# design.net
KiCad netlist of a schematic drawn in Altium Designer
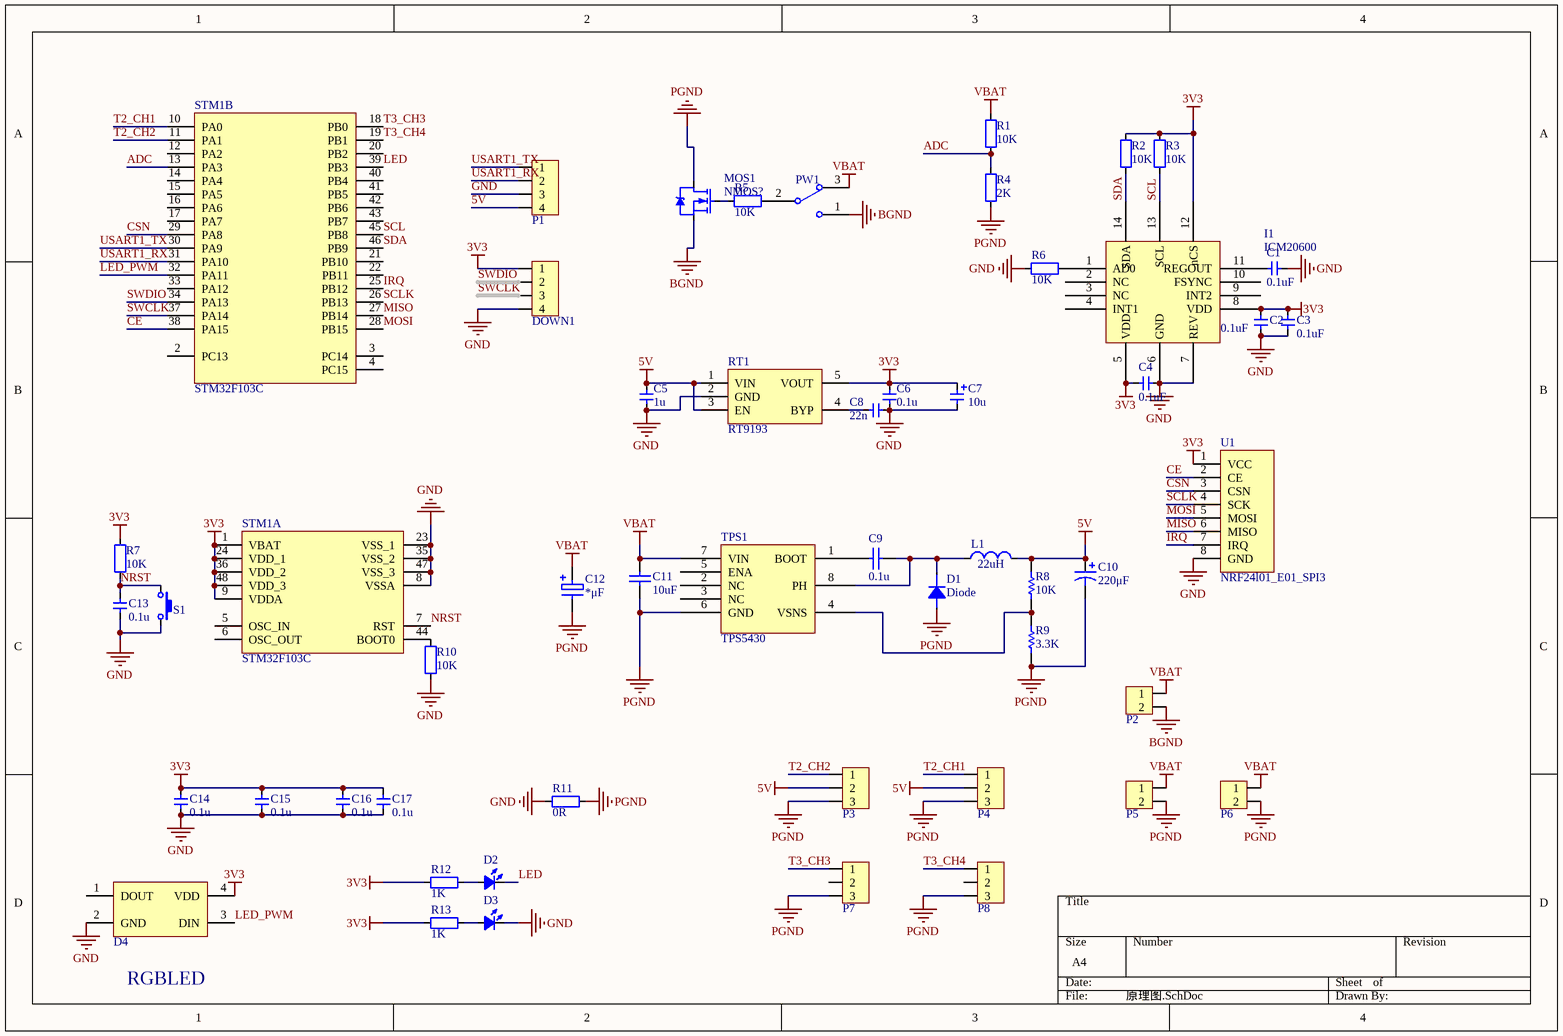
[diagram p0: 原理图.SchDoc]

(export (version "E")
  (design (tool "Eeschema 10.0.6"))
  (components
    (comp (ref "C1")
      (value "0.1uF")
      (footprint "PCB_PassiveCap:CAP_0603")
      (description "Capacitor")
      (fields (field (name "Comment") "Cap_0603"))
      (libsource (lib "SCH_Passive") (part "Cap_0603"))
    )
    (comp (ref "C2")
      (value "0.1uF")
      (footprint "PCB_PassiveCap:CAP_0603")
      (description "Capacitor")
      (fields (field (name "Comment") "Cap_0603"))
      (libsource (lib "SCH_Passive") (part "Cap_0603"))
    )
    (comp (ref "C3")
      (value "0.1uF")
      (footprint "PCB_PassiveCap:CAP_0603")
      (description "Capacitor")
      (fields (field (name "Comment") "Cap_0603"))
      (libsource (lib "SCH_Passive") (part "Cap_0603"))
    )
    (comp (ref "C4")
      (value "0.1uF")
      (footprint "PCB_PassiveCap:CAP_0603")
      (description "Capacitor")
      (fields (field (name "Comment") "Cap_0603"))
      (libsource (lib "SCH_Passive") (part "Cap_0603"))
    )
    (comp (ref "C5")
      (value "1u")
      (footprint "PCB_PassiveCap:CAP_0603")
      (description "Capacitor")
      (fields (field (name "Comment") "Cap_0603"))
      (libsource (lib "SCH_Passive") (part "Cap_0603"))
    )
    (comp (ref "C6")
      (value "0.1u")
      (footprint "PCB_PassiveCap:CAP_0603")
      (description "Capacitor")
      (fields (field (name "Comment") "Cap_0603"))
      (libsource (lib "SCH_Passive") (part "Cap_0603"))
    )
    (comp (ref "C7")
      (value "10u")
      (footprint "PCB_PassiveCap:CAP_TAN_P0805")
      (description "Capacitor")
      (fields (field (name "Comment") "Cap_Tan_0805"))
      (libsource (lib "SCH_Passive") (part "Cap_Tan_0805"))
    )
    (comp (ref "C8")
      (value "22n")
      (footprint "PCB_PassiveCap:CAP_0603")
      (description "Capacitor")
      (fields (field (name "Comment") "Cap_0603"))
      (libsource (lib "SCH_Passive") (part "Cap_0603"))
    )
    (comp (ref "C9")
      (value "0.1u")
      (footprint "CAP-MLCC-0603")
      (description "Capacitor")
      (fields (field (name "Comment") "Cap") (field (name "PUBLISHER") "Altium Limited"))
      (libsource (lib "K60-mainboard-v3.1") (part "Cap_1"))
    )
    (comp (ref "C10")
      (value "220μF")
      (footprint "CAP-TAN-6032/CAPC")
      (description "钽电容")
      (fields (field (name "PUBLISHER") "Altium Limited"))
      (libsource (lib "Libraries_2014_0618") (part "CAP-TAN"))
    )
    (comp (ref "C11")
      (value "10uF")
      (footprint "0805C")
      (description "Capacitor")
      (fields (field (name "Comment") "Cap") (field (name "PUBLISHER") "Altium Limited"))
      (libsource (lib "K60-mainboard-v3.1") (part "Cap"))
    )
    (comp (ref "C12")
      (value "*μF")
      (footprint "C_ELE")
      (description "电解电容")
      (fields (field (name "PUBLISHER") "Altium Limited"))
      (libsource (lib "Libraries_2014_0618") (part "CAP-ELE"))
    )
    (comp (ref "C13")
      (value "0.1u")
      (footprint "PCB_PassiveCap:CAP_0603")
      (description "Capacitor")
      (fields (field (name "Comment") "Cap_0603"))
      (libsource (lib "SCH_Passive") (part "Cap_0603"))
    )
    (comp (ref "C14")
      (value "0.1u")
      (footprint "PCB_PassiveCap:CAP_0603")
      (description "Capacitor")
      (fields (field (name "Comment") "Cap_0603"))
      (libsource (lib "SCH_Passive") (part "Cap_0603"))
    )
    (comp (ref "C15")
      (value "0.1u")
      (footprint "PCB_PassiveCap:CAP_0603")
      (description "Capacitor")
      (fields (field (name "Comment") "Cap_0603"))
      (libsource (lib "SCH_Passive") (part "Cap_0603"))
    )
    (comp (ref "C16")
      (value "0.1u")
      (footprint "PCB_PassiveCap:CAP_0603")
      (description "Capacitor")
      (fields (field (name "Comment") "Cap_0603"))
      (libsource (lib "SCH_Passive") (part "Cap_0603"))
    )
    (comp (ref "C17")
      (value "0.1u")
      (footprint "PCB_PassiveCap:CAP_0603")
      (description "Capacitor")
      (fields (field (name "Comment") "Cap_0603"))
      (libsource (lib "SCH_Passive") (part "Cap_0603"))
    )
    (comp (ref "D1") (value "Diode") (footprint "SS34") (libsource (lib "K60-mainboard-v3.1") (part "Diode")))
    (comp (ref "D2")
      (value "LED_0805")
      (footprint "PCB_ActiveLED:LED_0805_RED")
      (description "LED")
      (libsource (lib "SCH_Active") (part "LED_0805"))
    )
    (comp (ref "D3")
      (value "LED_0805")
      (footprint "PCB_ActiveLED:LED_0805_RED")
      (description "LED")
      (libsource (lib "SCH_Active") (part "LED_0805"))
    )
    (comp (ref "D4")
      (value "LED_3535_SK6812")
      (footprint "PCB_ActiveLED:LED_3535_4P")
      (description "LED")
      (libsource (lib "SCH_Active") (part "LED_3535_SK6812"))
    )
    (comp (ref "DOWN1")
      (value "HDR1x4_2.54")
      (footprint "PCB_ConnectorHDR:HDR1x4_2.54_180")
      (description "Header")
      (libsource (lib "SCH_ConnectorHDR") (part "HDR1x4_2.54"))
    )
    (comp (ref "I1")
      (value "ICM20600")
      (footprint "ICM20600")
      (libsource (lib "SCH_IntegratedCircuit") (part "ICM20600"))
    )
    (comp (ref "L1")
      (value "22uH")
      (footprint "CD74")
      (description "Inductor")
      (fields (field (name "Comment") "Ind-CD52"))
      (libsource (lib "SCH_Passive") (part "Ind_CD52"))
    )
    (comp (ref "MOS1")
      (value "NMOS?")
      (footprint "PCB_IntegratedCircuit:TO-252AA")
      (description "MOSFET")
      (fields (field (name "Comment") "MOSFET_N"))
      (libsource (lib "SCH_Active") (part "MOSFET_N"))
    )
    (comp (ref "P1")
      (value "HDR1x4_2.54")
      (footprint "PCB_ConnectorHDR:HDR1x4_2.54_180")
      (description "Header")
      (libsource (lib "SCH_ConnectorHDR") (part "HDR1x4_2.54"))
    )
    (comp (ref "P2") (value "Connector") (footprint "Green 2P") (libsource (lib "SCH_Connector") (part "2P")))
    (comp (ref "P3")
      (value "HDR1x3_2.54")
      (footprint "PCB_ConnectorHDR:HDR1X3_2.54_180")
      (description "Header")
      (libsource (lib "SCH_ConnectorHDR") (part "HDR1x3_2.54"))
    )
    (comp (ref "P4")
      (value "HDR1x3_2.54")
      (footprint "PCB_ConnectorHDR:HDR1X3_2.54_180")
      (description "Header")
      (libsource (lib "SCH_ConnectorHDR") (part "HDR1x3_2.54"))
    )
    (comp (ref "P5") (value "Connector") (footprint "2P_SMD") (libsource (lib "SCH_Connector") (part "2P")))
    (comp (ref "P6") (value "Connector") (footprint "2P_SMD") (libsource (lib "SCH_Connector") (part "2P")))
    (comp (ref "P7")
      (value "HDR1x3_2.54")
      (footprint "PCB_ConnectorHDR:HDR1X3_2.54_180")
      (description "Header")
      (libsource (lib "SCH_ConnectorHDR") (part "HDR1x3_2.54"))
    )
    (comp (ref "P8")
      (value "HDR1x3_2.54")
      (footprint "PCB_ConnectorHDR:HDR1X3_2.54_180")
      (description "Header")
      (libsource (lib "SCH_ConnectorHDR") (part "HDR1x3_2.54"))
    )
    (comp (ref "PW1")
      (value "SwitchSPDT_2.8x6.6_90")
      (footprint "PCB_Switch:SwitchSPDT_2.8X6.6_90")
      (description "Switch")
      (libsource (lib "SCH_Switch") (part "SwitchSPDT_2.8x6.6_90"))
    )
    (comp (ref "R1")
      (value "10K")
      (footprint "PCB_PassiveRes:RES_0603")
      (description "Resistor")
      (fields (field (name "Comment") "Res_0603"))
      (libsource (lib "") (part "Res_0603_1"))
    )
    (comp (ref "R2")
      (value "10K")
      (footprint "PCB_PassiveRes:RES_0603")
      (description "Resistor")
      (fields (field (name "Comment") "Res_0603"))
      (libsource (lib "SCH_Passive") (part "Res_0603"))
    )
    (comp (ref "R3")
      (value "10K")
      (footprint "PCB_PassiveRes:RES_0603")
      (description "Resistor")
      (fields (field (name "Comment") "Res_0603"))
      (libsource (lib "SCH_Passive") (part "Res_0603"))
    )
    (comp (ref "R4")
      (value "2K")
      (footprint "PCB_PassiveRes:RES_0603")
      (description "Resistor")
      (fields (field (name "Comment") "Res_0603"))
      (libsource (lib "") (part "Res_0603_1"))
    )
    (comp (ref "R5")
      (value "10K")
      (footprint "PCB_PassiveRes:RES_0603")
      (description "Resistor")
      (fields (field (name "Comment") "Res_0603"))
      (libsource (lib "") (part "Res_0603_2"))
    )
    (comp (ref "R6")
      (value "10K")
      (footprint "PCB_PassiveRes:RES_0603")
      (description "Resistor")
      (fields (field (name "Comment") "Res_0603"))
      (libsource (lib "") (part "Res_0603_2"))
    )
    (comp (ref "R7")
      (value "10K")
      (footprint "PCB_PassiveRes:RES_0603")
      (description "Resistor")
      (fields (field (name "Comment") "Res_0603"))
      (libsource (lib "SCH_Passive") (part "Res_0603"))
    )
    (comp (ref "R8")
      (value "10K")
      (footprint "RES-0603")
      (description "Resistor")
      (fields (field (name "Comment") "Res1") (field (name "PUBLISHER") "Altium Limited"))
      (libsource (lib "K60-mainboard-v3.1") (part "Res1"))
    )
    (comp (ref "R9")
      (value "3.3K")
      (footprint "RES-0603")
      (description "Resistor")
      (fields (field (name "Comment") "Res1") (field (name "PUBLISHER") "Altium Limited"))
      (libsource (lib "K60-mainboard-v3.1") (part "Res1"))
    )
    (comp (ref "R10")
      (value "10K")
      (footprint "PCB_PassiveRes:RES_0603")
      (description "Resistor")
      (fields (field (name "Comment") "Res_0603"))
      (libsource (lib "SCH_Passive") (part "Res_0603"))
    )
    (comp (ref "R11")
      (value "0R")
      (footprint "PCB_PassiveRes:RES_0603")
      (description "Resistor")
      (fields (field (name "Comment") "Res_0603"))
      (libsource (lib "") (part "Res_0603_2"))
    )
    (comp (ref "R12")
      (value "1K")
      (footprint "PCB_PassiveRes:RES_0603")
      (description "Resistor")
      (fields (field (name "Comment") "RES_0805"))
      (libsource (lib "SCH_Passive") (part "Res_0805"))
    )
    (comp (ref "R13")
      (value "1K")
      (footprint "PCB_PassiveRes:RES_0603")
      (description "Resistor")
      (fields (field (name "Comment") "RES_0805"))
      (libsource (lib "SCH_Passive") (part "Res_0805"))
    )
    (comp (ref "RT1")
      (value "RT9193")
      (footprint "PCB_IntegratedCircuit:SOT23-5")
      (description "Power")
      (libsource (lib "SCH_IntegratedCircuit") (part "RT9193"))
    )
    (comp (ref "S1")
      (value "ButtonTACT_3x4x2_180")
      (footprint "PCB_Switch:ButtonTACT_3x4x2_180H")
      (description "Button")
      (libsource (lib "SCH_Switch") (part "ButtonTACT_3x4x2_180"))
    )
    (comp (ref "STM1")
      (value "STM32F103C")
      (footprint "PCB_IntegratedCircuit:LQFP_P0.5_48")
      (description "MCU")
      (libsource (lib "SCH_IntegratedCircuit") (part "STM32F103C"))
    )
    (comp (ref "TPS1")
      (value "TPS5430")
      (footprint "SOP_E150_8 -with_PADs")
      (libsource (lib "SCH_IntegratedCircuit") (part "TPS5430"))
    )
    (comp (ref "U1")
      (value "NRF24l01_E01_SPI3")
      (footprint "E01-ML01SP2")
      (libsource (lib "SCH_Module") (part "NRF24l01_E01_SPI2"))
    )
  )
  (nets
    (net (code "1") (name "/ADC") (class "Default")
      (node (ref "R1") (pin "1") (pinfunction "1_1") (pintype "passive"))
      (node (ref "R4") (pin "2") (pinfunction "2_2") (pintype "passive"))
      (node (ref "STM1") (pin "13") (pinfunction "PA3_13") (pintype "passive"))
    )
    (net (code "2") (name "/CE") (class "Default")
      (node (ref "STM1") (pin "38") (pinfunction "PA15_38") (pintype "passive"))
      (node (ref "U1") (pin "2") (pinfunction "CE_2") (pintype "passive"))
    )
    (net (code "3") (name "/CSN") (class "Default")
      (node (ref "STM1") (pin "29") (pinfunction "PA8_29") (pintype "passive"))
      (node (ref "U1") (pin "3") (pinfunction "CSN_3") (pintype "passive"))
    )
    (net (code "4") (name "/IRQ") (class "Default")
      (node (ref "STM1") (pin "25") (pinfunction "PB12_25") (pintype "passive"))
      (node (ref "U1") (pin "7") (pinfunction "IRQ_7") (pintype "passive"))
    )
    (net (code "5") (name "/LED") (class "Default")
      (node (ref "D2") (pin "2") (pinfunction "K_2") (pintype "passive"))
      (node (ref "STM1") (pin "39") (pinfunction "PB3_39") (pintype "passive"))
    )
    (net (code "6") (name "/LED_PWM") (class "Default")
      (node (ref "D4") (pin "3") (pinfunction "DIN_3") (pintype "passive"))
      (node (ref "STM1") (pin "32") (pinfunction "PA11_32") (pintype "passive"))
    )
    (net (code "7") (name "/MISO") (class "Default")
      (node (ref "STM1") (pin "27") (pinfunction "PB14_27") (pintype "passive"))
      (node (ref "U1") (pin "6") (pinfunction "MISO_6") (pintype "passive"))
    )
    (net (code "8") (name "/MOSI") (class "Default")
      (node (ref "STM1") (pin "28") (pinfunction "PB15_28") (pintype "passive"))
      (node (ref "U1") (pin "5") (pinfunction "MOSI_5") (pintype "passive"))
    )
    (net (code "9") (name "/NRST") (class "Default")
      (node (ref "C13") (pin "2") (pinfunction "2_2") (pintype "passive"))
      (node (ref "R7") (pin "2") (pinfunction "2_2") (pintype "passive"))
      (node (ref "S1") (pin "1") (pinfunction "1_1") (pintype "passive"))
      (node (ref "STM1") (pin "7") (pinfunction "RST_7") (pintype "passive"))
    )
    (net (code "10") (name "/SCL") (class "Default")
      (node (ref "I1") (pin "13") (pinfunction "SCL_13") (pintype "passive"))
      (node (ref "R3") (pin "2") (pinfunction "2_2") (pintype "passive"))
      (node (ref "STM1") (pin "45") (pinfunction "PB8_45") (pintype "passive"))
    )
    (net (code "11") (name "/SCLK") (class "Default")
      (node (ref "STM1") (pin "26") (pinfunction "PB13_26") (pintype "passive"))
      (node (ref "U1") (pin "4") (pinfunction "SCK_4") (pintype "passive"))
    )
    (net (code "12") (name "/SDA") (class "Default")
      (node (ref "I1") (pin "14") (pinfunction "SDA_14") (pintype "passive"))
      (node (ref "R2") (pin "2") (pinfunction "2_2") (pintype "passive"))
      (node (ref "STM1") (pin "46") (pinfunction "PB9_46") (pintype "passive"))
    )
    (net (code "13") (name "/SWCLK") (class "Default")
      (node (ref "DOWN1") (pin "3") (pinfunction "3_3") (pintype "passive"))
      (node (ref "STM1") (pin "37") (pinfunction "PA14_37") (pintype "passive"))
    )
    (net (code "14") (name "/SWDIO") (class "Default")
      (node (ref "DOWN1") (pin "2") (pinfunction "2_2") (pintype "passive"))
      (node (ref "STM1") (pin "34") (pinfunction "PA13_34") (pintype "passive"))
    )
    (net (code "15") (name "/T2_CH1") (class "Default")
      (node (ref "P4") (pin "1") (pinfunction "1_1") (pintype "passive"))
      (node (ref "STM1") (pin "10") (pinfunction "PA0_10") (pintype "passive"))
    )
    (net (code "16") (name "/T2_CH2") (class "Default")
      (node (ref "P3") (pin "1") (pinfunction "1_1") (pintype "passive"))
      (node (ref "STM1") (pin "11") (pinfunction "PA1_11") (pintype "passive"))
    )
    (net (code "17") (name "/T3_CH3") (class "Default")
      (node (ref "P7") (pin "1") (pinfunction "1_1") (pintype "passive"))
      (node (ref "STM1") (pin "18") (pinfunction "PB0_18") (pintype "passive"))
    )
    (net (code "18") (name "/T3_CH4") (class "Default")
      (node (ref "P8") (pin "1") (pinfunction "1_1") (pintype "passive"))
      (node (ref "STM1") (pin "19") (pinfunction "PB1_19") (pintype "passive"))
    )
    (net (code "19") (name "/USART1_RX") (class "Default")
      (node (ref "P1") (pin "2") (pinfunction "2_2") (pintype "passive"))
      (node (ref "STM1") (pin "31") (pinfunction "PA10_31") (pintype "passive"))
    )
    (net (code "20") (name "/USART1_TX") (class "Default")
      (node (ref "P1") (pin "1") (pinfunction "1_1") (pintype "passive"))
      (node (ref "STM1") (pin "30") (pinfunction "PA9_30") (pintype "passive"))
    )
    (net (code "21") (name "3V3") (class "Default")
      (node (ref "C14") (pin "2") (pinfunction "2_2") (pintype "passive"))
      (node (ref "C15") (pin "2") (pinfunction "2_2") (pintype "passive"))
      (node (ref "C16") (pin "2") (pinfunction "2_2") (pintype "passive"))
      (node (ref "C17") (pin "2") (pinfunction "2_2") (pintype "passive"))
      (node (ref "C2") (pin "1") (pinfunction "1_1") (pintype "passive"))
      (node (ref "C3") (pin "1") (pinfunction "1_1") (pintype "passive"))
      (node (ref "C4") (pin "2") (pinfunction "2_2") (pintype "passive"))
      (node (ref "C6") (pin "2") (pinfunction "2_2") (pintype "passive"))
      (node (ref "C7") (pin "1") (pinfunction "1_1") (pintype "passive"))
      (node (ref "D4") (pin "4") (pinfunction "VDD_4") (pintype "passive"))
      (node (ref "DOWN1") (pin "1") (pinfunction "1_1") (pintype "passive"))
      (node (ref "I1") (pin "12") (pinfunction "nCS_12") (pintype "passive"))
      (node (ref "I1") (pin "5") (pinfunction "VDD_5") (pintype "passive"))
      (node (ref "I1") (pin "8") (pinfunction "VDD_8") (pintype "passive"))
      (node (ref "R12") (pin "1") (pinfunction "1_1") (pintype "passive"))
      (node (ref "R13") (pin "1") (pinfunction "1_1") (pintype "passive"))
      (node (ref "R2") (pin "1") (pinfunction "1_1") (pintype "passive"))
      (node (ref "R3") (pin "1") (pinfunction "1_1") (pintype "passive"))
      (node (ref "R7") (pin "1") (pinfunction "1_1") (pintype "passive"))
      (node (ref "RT1") (pin "5") (pinfunction "VOUT_5") (pintype "passive"))
      (node (ref "STM1") (pin "1") (pinfunction "VBAT_1") (pintype "passive"))
      (node (ref "STM1") (pin "24") (pinfunction "VDD_1_24") (pintype "passive"))
      (node (ref "STM1") (pin "36") (pinfunction "VDD_2_36") (pintype "passive"))
      (node (ref "STM1") (pin "48") (pinfunction "VDD_3_48") (pintype "passive"))
      (node (ref "STM1") (pin "9") (pinfunction "VDDA_9") (pintype "passive"))
      (node (ref "U1") (pin "1") (pinfunction "VCC_1") (pintype "passive"))
    )
    (net (code "22") (name "5V") (class "Default")
      (node (ref "C10") (pin "1") (pinfunction "1_1") (pintype "passive"))
      (node (ref "C5") (pin "2") (pinfunction "2_2") (pintype "passive"))
      (node (ref "L1") (pin "2") (pinfunction "2_2") (pintype "passive"))
      (node (ref "P1") (pin "4") (pinfunction "4_4") (pintype "passive"))
      (node (ref "P3") (pin "2") (pinfunction "2_2") (pintype "passive"))
      (node (ref "P4") (pin "2") (pinfunction "2_2") (pintype "passive"))
      (node (ref "R8") (pin "2") (pinfunction "2_2") (pintype "passive"))
      (node (ref "RT1") (pin "1") (pinfunction "VIN_1") (pintype "passive"))
      (node (ref "RT1") (pin "3") (pinfunction "EN_3") (pintype "power_in"))
    )
    (net (code "23") (name "BGND") (class "Default")
      (node (ref "MOS1") (pin "3") (pinfunction "S_3") (pintype "passive"))
      (node (ref "P2") (pin "2") (pinfunction "2_2") (pintype "passive"))
      (node (ref "PW1") (pin "1") (pinfunction "1_1") (pintype "passive"))
    )
    (net (code "24") (name "GND") (class "Default")
      (node (ref "C1") (pin "2") (pinfunction "2_2") (pintype "passive"))
      (node (ref "C13") (pin "1") (pinfunction "1_1") (pintype "passive"))
      (node (ref "C14") (pin "1") (pinfunction "1_1") (pintype "passive"))
      (node (ref "C15") (pin "1") (pinfunction "1_1") (pintype "passive"))
      (node (ref "C16") (pin "1") (pinfunction "1_1") (pintype "passive"))
      (node (ref "C17") (pin "1") (pinfunction "1_1") (pintype "passive"))
      (node (ref "C2") (pin "2") (pinfunction "2_2") (pintype "passive"))
      (node (ref "C3") (pin "2") (pinfunction "2_2") (pintype "passive"))
      (node (ref "C4") (pin "1") (pinfunction "1_1") (pintype "passive"))
      (node (ref "C5") (pin "1") (pinfunction "1_1") (pintype "passive"))
      (node (ref "C6") (pin "1") (pinfunction "1_1") (pintype "passive"))
      (node (ref "C7") (pin "2") (pinfunction "2_2") (pintype "passive"))
      (node (ref "C8") (pin "1") (pinfunction "1_1") (pintype "passive"))
      (node (ref "D3") (pin "2") (pinfunction "K_2") (pintype "passive"))
      (node (ref "D4") (pin "2") (pinfunction "GND_2") (pintype "passive"))
      (node (ref "DOWN1") (pin "4") (pinfunction "4_4") (pintype "passive"))
      (node (ref "I1") (pin "6") (pinfunction "GND_6") (pintype "passive"))
      (node (ref "I1") (pin "7") (pinfunction "REV_7") (pintype "passive"))
      (node (ref "P1") (pin "3") (pinfunction "3_3") (pintype "passive"))
      (node (ref "R10") (pin "2") (pinfunction "2_2") (pintype "passive"))
      (node (ref "R11") (pin "1") (pinfunction "1_1") (pintype "passive"))
      (node (ref "R6") (pin "1") (pinfunction "1_1") (pintype "passive"))
      (node (ref "RT1") (pin "2") (pinfunction "GND_2") (pintype "passive"))
      (node (ref "S1") (pin "2") (pinfunction "2_2") (pintype "passive"))
      (node (ref "STM1") (pin "23") (pinfunction "VSS_1_23") (pintype "passive"))
      (node (ref "STM1") (pin "35") (pinfunction "VSS_2_35") (pintype "passive"))
      (node (ref "STM1") (pin "47") (pinfunction "VSS_3_47") (pintype "passive"))
      (node (ref "STM1") (pin "8") (pinfunction "VSSA_8") (pintype "passive"))
      (node (ref "U1") (pin "8") (pinfunction "GND_8") (pintype "passive"))
    )
    (net (code "25") (name "Net-(D1-2)") (class "Default")
      (node (ref "C9") (pin "1") (pinfunction "1_1") (pintype "passive"))
      (node (ref "D1") (pin "K") (pinfunction "2_K") (pintype "passive"))
      (node (ref "L1") (pin "1") (pinfunction "1_1") (pintype "passive"))
      (node (ref "TPS1") (pin "8") (pinfunction "PH_8") (pintype "passive"))
    )
    (net (code "26") (name "Net-(D2-A)") (class "Default")
      (node (ref "D2") (pin "1") (pinfunction "A_1") (pintype "passive"))
      (node (ref "R12") (pin "2") (pinfunction "2_2") (pintype "passive"))
    )
    (net (code "27") (name "Net-(D3-A)") (class "Default")
      (node (ref "D3") (pin "1") (pinfunction "A_1") (pintype "passive"))
      (node (ref "R13") (pin "2") (pinfunction "2_2") (pintype "passive"))
    )
    (net (code "28") (name "Net-(I1-AD0)") (class "Default")
      (node (ref "I1") (pin "1") (pinfunction "AD0_1") (pintype "passive"))
      (node (ref "R6") (pin "2") (pinfunction "2_2") (pintype "passive"))
    )
    (net (code "29") (name "Net-(I1-REGOUT)") (class "Default")
      (node (ref "C1") (pin "1") (pinfunction "1_1") (pintype "passive"))
      (node (ref "I1") (pin "11") (pinfunction "REGOUT_11") (pintype "passive"))
    )
    (net (code "30") (name "Net-(MOS1-G)") (class "Default")
      (node (ref "MOS1") (pin "1") (pinfunction "G_1") (pintype "passive"))
      (node (ref "R5") (pin "1") (pinfunction "1_1") (pintype "passive"))
    )
    (net (code "31") (name "Net-(PW1-Pad2)") (class "Default")
      (node (ref "PW1") (pin "2") (pinfunction "2_2") (pintype "passive"))
      (node (ref "R5") (pin "2") (pinfunction "2_2") (pintype "passive"))
    )
    (net (code "32") (name "Net-(RT1-BYP)") (class "Default")
      (node (ref "C8") (pin "2") (pinfunction "2_2") (pintype "passive"))
      (node (ref "RT1") (pin "4") (pinfunction "BYP_4") (pintype "passive"))
    )
    (net (code "33") (name "Net-(STM1A-BOOT0)") (class "Default")
      (node (ref "R10") (pin "1") (pinfunction "1_1") (pintype "passive"))
      (node (ref "STM1") (pin "44") (pinfunction "BOOT0_44") (pintype "passive"))
    )
    (net (code "34") (name "Net-(TPS1-BOOT)") (class "Default")
      (node (ref "C9") (pin "2") (pinfunction "2_2") (pintype "passive"))
      (node (ref "TPS1") (pin "1") (pinfunction "BOOT_1") (pintype "passive"))
    )
    (net (code "35") (name "Net-(TPS1-VSNS)") (class "Default")
      (node (ref "R8") (pin "1") (pinfunction "1_1") (pintype "passive"))
      (node (ref "R9") (pin "2") (pinfunction "2_2") (pintype "passive"))
      (node (ref "TPS1") (pin "4") (pinfunction "VSNS_4") (pintype "passive"))
    )
    (net (code "36") (name "PGND") (class "Default")
      (node (ref "C10") (pin "2") (pinfunction "2_2") (pintype "passive"))
      (node (ref "C11") (pin "1") (pinfunction "1_1") (pintype "passive"))
      (node (ref "C12") (pin "2") (pinfunction "2_2") (pintype "passive"))
      (node (ref "D1") (pin "A") (pinfunction "1_A") (pintype "passive"))
      (node (ref "MOS1") (pin "4") (pinfunction "D_4") (pintype "passive"))
      (node (ref "P3") (pin "3") (pinfunction "3_3") (pintype "passive"))
      (node (ref "P4") (pin "3") (pinfunction "3_3") (pintype "passive"))
      (node (ref "P5") (pin "2") (pinfunction "2_2") (pintype "passive"))
      (node (ref "P6") (pin "2") (pinfunction "2_2") (pintype "passive"))
      (node (ref "P7") (pin "3") (pinfunction "3_3") (pintype "passive"))
      (node (ref "P8") (pin "3") (pinfunction "3_3") (pintype "passive"))
      (node (ref "R11") (pin "2") (pinfunction "2_2") (pintype "passive"))
      (node (ref "R4") (pin "1") (pinfunction "1_1") (pintype "passive"))
      (node (ref "R9") (pin "1") (pinfunction "1_1") (pintype "passive"))
      (node (ref "TPS1") (pin "6") (pinfunction "GND_6") (pintype "passive"))
    )
    (net (code "37") (name "VBAT") (class "Default")
      (node (ref "C11") (pin "2") (pinfunction "2_2") (pintype "passive"))
      (node (ref "C12") (pin "1") (pinfunction "1_1") (pintype "passive"))
      (node (ref "P2") (pin "1") (pinfunction "1_1") (pintype "passive"))
      (node (ref "P5") (pin "1") (pinfunction "1_1") (pintype "passive"))
      (node (ref "P6") (pin "1") (pinfunction "1_1") (pintype "passive"))
      (node (ref "PW1") (pin "3") (pinfunction "3_3") (pintype "passive"))
      (node (ref "R1") (pin "2") (pinfunction "2_2") (pintype "passive"))
      (node (ref "TPS1") (pin "7") (pinfunction "VIN_7") (pintype "passive"))
    )
    (net (code "38") (name "unconnected-(D4-DOUT-Pad1)") (class "Default")
      (node (ref "D4") (pin "1") (pinfunction "DOUT_1") (pintype "passive"))
    )
    (net (code "39") (name "unconnected-(I1-FSYNC-Pad10)") (class "Default")
      (node (ref "I1") (pin "10") (pinfunction "FSYNC_10") (pintype "passive"))
    )
    (net (code "40") (name "unconnected-(I1-INT1-Pad4)") (class "Default")
      (node (ref "I1") (pin "4") (pinfunction "INT1_4") (pintype "passive"))
    )
    (net (code "41") (name "unconnected-(I1-INT2-Pad9)") (class "Default")
      (node (ref "I1") (pin "9") (pinfunction "INT2_9") (pintype "passive"))
    )
    (net (code "42") (name "unconnected-(I1-NC-Pad2)") (class "Default")
      (node (ref "I1") (pin "2") (pinfunction "NC_2") (pintype "passive"))
    )
    (net (code "43") (name "unconnected-(I1-NC-Pad3)") (class "Default")
      (node (ref "I1") (pin "3") (pinfunction "NC_3") (pintype "passive"))
    )
    (net (code "44") (name "unconnected-(P7-Pad2)") (class "Default")
      (node (ref "P7") (pin "2") (pinfunction "2_2") (pintype "passive"))
    )
    (net (code "45") (name "unconnected-(P8-Pad2)") (class "Default")
      (node (ref "P8") (pin "2") (pinfunction "2_2") (pintype "passive"))
    )
    (net (code "46") (name "unconnected-(STM1A-OSC_IN-Pad5)") (class "Default")
      (node (ref "STM1") (pin "5") (pinfunction "OSC_IN_5") (pintype "passive"))
    )
    (net (code "47") (name "unconnected-(STM1A-OSC_OUT-Pad6)") (class "Default")
      (node (ref "STM1") (pin "6") (pinfunction "OSC_OUT_6") (pintype "passive"))
    )
    (net (code "48") (name "unconnected-(STM1B-PA2-Pad12)") (class "Default")
      (node (ref "STM1") (pin "12") (pinfunction "PA2_12") (pintype "passive"))
    )
    (net (code "49") (name "unconnected-(STM1B-PA4-Pad14)") (class "Default")
      (node (ref "STM1") (pin "14") (pinfunction "PA4_14") (pintype "passive"))
    )
    (net (code "50") (name "unconnected-(STM1B-PA5-Pad15)") (class "Default")
      (node (ref "STM1") (pin "15") (pinfunction "PA5_15") (pintype "passive"))
    )
    (net (code "51") (name "unconnected-(STM1B-PA6-Pad16)") (class "Default")
      (node (ref "STM1") (pin "16") (pinfunction "PA6_16") (pintype "passive"))
    )
    (net (code "52") (name "unconnected-(STM1B-PA7-Pad17)") (class "Default")
      (node (ref "STM1") (pin "17") (pinfunction "PA7_17") (pintype "passive"))
    )
    (net (code "53") (name "unconnected-(STM1B-PA12-Pad33)") (class "Default")
      (node (ref "STM1") (pin "33") (pinfunction "PA12_33") (pintype "passive"))
    )
    (net (code "54") (name "unconnected-(STM1B-PB2-Pad20)") (class "Default")
      (node (ref "STM1") (pin "20") (pinfunction "PB2_20") (pintype "passive"))
    )
    (net (code "55") (name "unconnected-(STM1B-PB4-Pad40)") (class "Default")
      (node (ref "STM1") (pin "40") (pinfunction "PB4_40") (pintype "passive"))
    )
    (net (code "56") (name "unconnected-(STM1B-PB5-Pad41)") (class "Default")
      (node (ref "STM1") (pin "41") (pinfunction "PB5_41") (pintype "passive"))
    )
    (net (code "57") (name "unconnected-(STM1B-PB6-Pad42)") (class "Default")
      (node (ref "STM1") (pin "42") (pinfunction "PB6_42") (pintype "passive"))
    )
    (net (code "58") (name "unconnected-(STM1B-PB7-Pad43)") (class "Default")
      (node (ref "STM1") (pin "43") (pinfunction "PB7_43") (pintype "passive"))
    )
    (net (code "59") (name "unconnected-(STM1B-PB10-Pad21)") (class "Default")
      (node (ref "STM1") (pin "21") (pinfunction "PB10_21") (pintype "passive"))
    )
    (net (code "60") (name "unconnected-(STM1B-PB11-Pad22)") (class "Default")
      (node (ref "STM1") (pin "22") (pinfunction "PB11_22") (pintype "passive"))
    )
    (net (code "61") (name "unconnected-(STM1B-PC13-Pad2)") (class "Default")
      (node (ref "STM1") (pin "2") (pinfunction "PC13_2") (pintype "passive"))
    )
    (net (code "62") (name "unconnected-(STM1B-PC14-Pad3)") (class "Default")
      (node (ref "STM1") (pin "3") (pinfunction "PC14_3") (pintype "passive"))
    )
    (net (code "63") (name "unconnected-(STM1B-PC15-Pad4)") (class "Default")
      (node (ref "STM1") (pin "4") (pinfunction "PC15_4") (pintype "passive"))
    )
    (net (code "64") (name "unconnected-(TPS1-ENA-Pad5)") (class "Default")
      (node (ref "TPS1") (pin "5") (pinfunction "ENA_5") (pintype "passive"))
    )
    (net (code "65") (name "unconnected-(TPS1-NC-Pad2)") (class "Default")
      (node (ref "TPS1") (pin "2") (pinfunction "NC_2") (pintype "passive"))
    )
    (net (code "66") (name "unconnected-(TPS1-NC-Pad3)") (class "Default")
      (node (ref "TPS1") (pin "3") (pinfunction "NC_3") (pintype "passive"))
    )
  )
)
